# Neuro.net
KiCad netlist of a schematic drawn in EAGLE
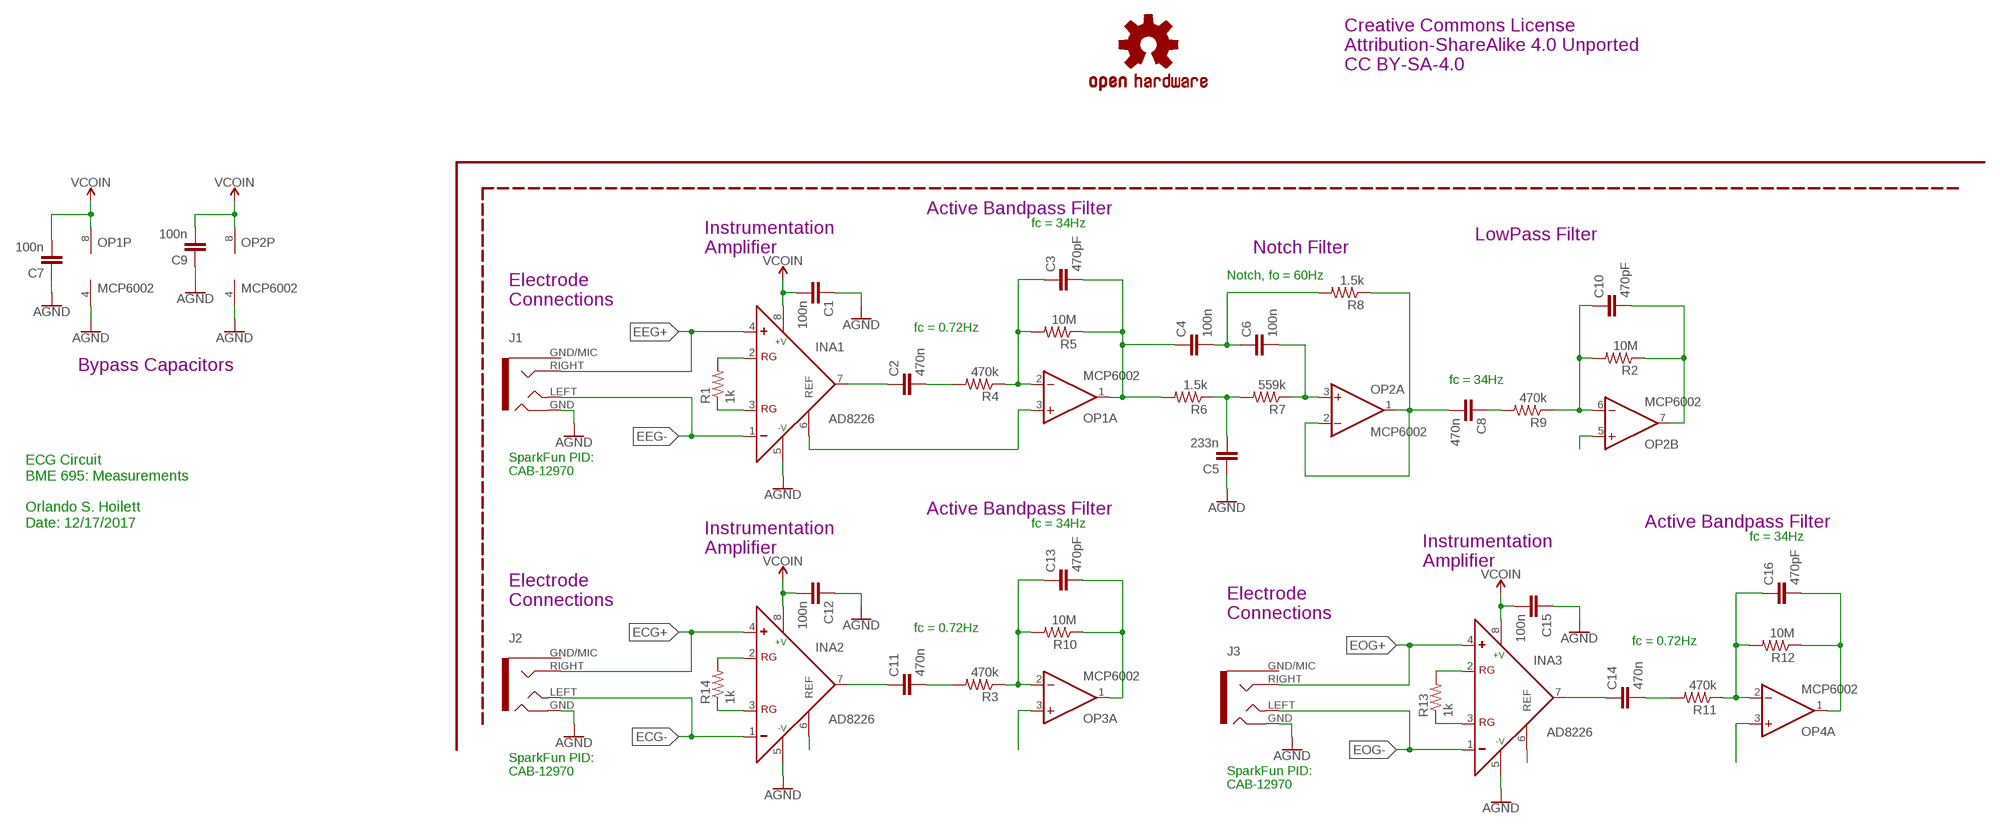
[diagram p0: schematic, sheet 1]

(export (version "E")
  (design (tool "Eeschema 10.0.6"))
  (components
    (comp (ref "C1")
      (value "100n")
      (footprint "eagle-import:C0402")
      (libsource (lib "eagle-import") (part "CAPACITOR0402"))
    )
    (comp (ref "C2")
      (value "470n")
      (footprint "eagle-import:C0402")
      (libsource (lib "eagle-import") (part "CAPACITOR0402"))
    )
    (comp (ref "C3")
      (value "470pF")
      (footprint "eagle-import:C0402")
      (libsource (lib "eagle-import") (part "CAPACITOR0402"))
    )
    (comp (ref "C4")
      (value "100n")
      (footprint "eagle-import:C0402")
      (libsource (lib "eagle-import") (part "CAPACITOR0402"))
    )
    (comp (ref "C5")
      (value "233n")
      (footprint "eagle-import:C0402")
      (libsource (lib "eagle-import") (part "CAPACITOR0402"))
    )
    (comp (ref "C6")
      (value "100n")
      (footprint "eagle-import:C0402")
      (libsource (lib "eagle-import") (part "CAPACITOR0402"))
    )
    (comp (ref "C7")
      (value "100n")
      (footprint "eagle-import:C0402")
      (libsource (lib "eagle-import") (part "CAPACITOR0402"))
    )
    (comp (ref "C8")
      (value "470n")
      (footprint "eagle-import:C0402")
      (libsource (lib "eagle-import") (part "CAPACITOR0402"))
    )
    (comp (ref "C9")
      (value "100n")
      (footprint "eagle-import:C0402")
      (libsource (lib "eagle-import") (part "CAPACITOR0402"))
    )
    (comp (ref "C10")
      (value "470pF")
      (footprint "eagle-import:C0402")
      (libsource (lib "eagle-import") (part "CAPACITOR0402"))
    )
    (comp (ref "C11")
      (value "470n")
      (footprint "eagle-import:C0402")
      (libsource (lib "eagle-import") (part "CAPACITOR0402"))
    )
    (comp (ref "C12")
      (value "100n")
      (footprint "eagle-import:C0402")
      (libsource (lib "eagle-import") (part "CAPACITOR0402"))
    )
    (comp (ref "C13")
      (value "470pF")
      (footprint "eagle-import:C0402")
      (libsource (lib "eagle-import") (part "CAPACITOR0402"))
    )
    (comp (ref "C14")
      (value "470n")
      (footprint "eagle-import:C0402")
      (libsource (lib "eagle-import") (part "CAPACITOR0402"))
    )
    (comp (ref "C15")
      (value "100n")
      (footprint "eagle-import:C0402")
      (libsource (lib "eagle-import") (part "CAPACITOR0402"))
    )
    (comp (ref "C16")
      (value "470pF")
      (footprint "eagle-import:C0402")
      (libsource (lib "eagle-import") (part "CAPACITOR0402"))
    )
    (comp (ref "INA1")
      (value "AD8226")
      (footprint "eagle-import:MSOP08")
      (libsource (lib "eagle-import") (part "INA-A"))
    )
    (comp (ref "INA2")
      (value "AD8226")
      (footprint "eagle-import:MSOP08")
      (libsource (lib "eagle-import") (part "INA-A"))
    )
    (comp (ref "INA3")
      (value "AD8226")
      (footprint "eagle-import:MSOP08")
      (libsource (lib "eagle-import") (part "INA-A"))
    )
    (comp (ref "J1")
      (value "AUDIO_JACK_TRRSSMD_RA")
      (footprint "eagle-import:AUDIO_JACK_3.5MM_TRRS_SMD_RA")
      (libsource (lib "eagle-import") (part "AUDIO_JACK_TRRSSMD_RA"))
    )
    (comp (ref "J2")
      (value "AUDIO_JACK_TRRSSMD_RA")
      (footprint "eagle-import:AUDIO_JACK_3.5MM_TRRS_SMD_RA")
      (libsource (lib "eagle-import") (part "AUDIO_JACK_TRRSSMD_RA"))
    )
    (comp (ref "J3")
      (value "AUDIO_JACK_TRRSSMD_RA")
      (footprint "eagle-import:AUDIO_JACK_3.5MM_TRRS_SMD_RA")
      (libsource (lib "eagle-import") (part "AUDIO_JACK_TRRSSMD_RA"))
    )
    (comp (ref "LOGO1")
      (value "OSHW-LOGOS")
      (footprint "eagle-import:OSHW-LOGO-S")
      (libsource (lib "eagle-import") (part "OSHW-LOGOS"))
    )
    (comp (ref "OP1")
      (value "MCP6002")
      (footprint "eagle-import:MSOP08")
      (fields (field (name "MF") "ALTERA CORPORATION") (field (name "MPN") "AD8607ARMZ-REEL"))
      (libsource (lib "eagle-import") (part "OP-DUALRM"))
    )
    (comp (ref "OP2")
      (value "MCP6002")
      (footprint "eagle-import:MSOP08")
      (fields (field (name "MF") "ALTERA CORPORATION") (field (name "MPN") "AD8607ARMZ-REEL"))
      (libsource (lib "eagle-import") (part "OP-DUALRM"))
    )
    (comp (ref "OP3")
      (value "MCP6002")
      (footprint "eagle-import:MSOP08")
      (fields (field (name "MF") "ALTERA CORPORATION") (field (name "MPN") "AD8607ARMZ-REEL"))
      (libsource (lib "eagle-import") (part "OP-DUALRM"))
    )
    (comp (ref "OP4")
      (value "MCP6002")
      (footprint "eagle-import:MSOP08")
      (fields (field (name "MF") "ALTERA CORPORATION") (field (name "MPN") "AD8607ARMZ-REEL"))
      (libsource (lib "eagle-import") (part "OP-DUALRM"))
    )
    (comp (ref "R1")
      (value "1k")
      (footprint "eagle-import:R0402")
      (libsource (lib "eagle-import") (part "RESISTOR0402"))
    )
    (comp (ref "R2")
      (value "10M")
      (footprint "eagle-import:R0402")
      (libsource (lib "eagle-import") (part "RESISTOR0402"))
    )
    (comp (ref "R3")
      (value "470k")
      (footprint "eagle-import:R0402")
      (libsource (lib "eagle-import") (part "RESISTOR0402"))
    )
    (comp (ref "R4")
      (value "470k")
      (footprint "eagle-import:R0402")
      (libsource (lib "eagle-import") (part "RESISTOR0402"))
    )
    (comp (ref "R5")
      (value "10M")
      (footprint "eagle-import:R0402")
      (libsource (lib "eagle-import") (part "RESISTOR0402"))
    )
    (comp (ref "R6")
      (value "1.5k")
      (footprint "eagle-import:R0402")
      (libsource (lib "eagle-import") (part "RESISTOR0402"))
    )
    (comp (ref "R7")
      (value "559k")
      (footprint "eagle-import:R0402")
      (libsource (lib "eagle-import") (part "RESISTOR0402"))
    )
    (comp (ref "R8")
      (value "1.5k")
      (footprint "eagle-import:R0402")
      (libsource (lib "eagle-import") (part "RESISTOR0402"))
    )
    (comp (ref "R9")
      (value "470k")
      (footprint "eagle-import:R0402")
      (libsource (lib "eagle-import") (part "RESISTOR0402"))
    )
    (comp (ref "R10")
      (value "10M")
      (footprint "eagle-import:R0402")
      (libsource (lib "eagle-import") (part "RESISTOR0402"))
    )
    (comp (ref "R11")
      (value "470k")
      (footprint "eagle-import:R0402")
      (libsource (lib "eagle-import") (part "RESISTOR0402"))
    )
    (comp (ref "R12")
      (value "10M")
      (footprint "eagle-import:R0402")
      (libsource (lib "eagle-import") (part "RESISTOR0402"))
    )
    (comp (ref "R13")
      (value "1k")
      (footprint "eagle-import:R0402")
      (libsource (lib "eagle-import") (part "RESISTOR0402"))
    )
    (comp (ref "R14")
      (value "1k")
      (footprint "eagle-import:R0402")
      (libsource (lib "eagle-import") (part "RESISTOR0402"))
    )
  )
  (nets
    (net (code "1") (name "AGND") (class "Default")
      (node (ref "C1") (pin "1") (pinfunction "1_1") (pintype "passive"))
      (node (ref "C12") (pin "1") (pinfunction "1_1") (pintype "passive"))
      (node (ref "C15") (pin "1") (pinfunction "1_1") (pintype "passive"))
      (node (ref "C5") (pin "1") (pinfunction "1_1") (pintype "passive"))
      (node (ref "C7") (pin "1") (pinfunction "1_1") (pintype "passive"))
      (node (ref "C9") (pin "1") (pinfunction "1_1") (pintype "passive"))
      (node (ref "INA1") (pin "5") (pinfunction "-V_5") (pintype "power_in"))
      (node (ref "INA2") (pin "5") (pinfunction "-V_5") (pintype "power_in"))
      (node (ref "INA3") (pin "5") (pinfunction "-V_5") (pintype "power_in"))
      (node (ref "J1") (pin "GND") (pinfunction "RING2_GND") (pintype "bidirectional"))
      (node (ref "J2") (pin "GND") (pinfunction "RING2_GND") (pintype "bidirectional"))
      (node (ref "J3") (pin "GND") (pinfunction "RING2_GND") (pintype "bidirectional"))
      (node (ref "OP1") (pin "4") (pinfunction "V-_4") (pintype "power_in"))
      (node (ref "OP2") (pin "4") (pinfunction "V-_4") (pintype "power_in"))
    )
    (net (code "2") (name "ECG+") (class "Default")
      (node (ref "INA2") (pin "4") (pinfunction "IN+_4") (pintype "input"))
      (node (ref "J2") (pin "RIGHT") (pinfunction "RING1_RIGHT") (pintype "bidirectional"))
    )
    (net (code "3") (name "ECG-") (class "Default")
      (node (ref "INA2") (pin "1") (pinfunction "IN-_1") (pintype "input"))
      (node (ref "J2") (pin "LEFT") (pinfunction "TIP_LEFT") (pintype "bidirectional"))
    )
    (net (code "4") (name "EEG+") (class "Default")
      (node (ref "INA1") (pin "4") (pinfunction "IN+_4") (pintype "input"))
      (node (ref "J1") (pin "RIGHT") (pinfunction "RING1_RIGHT") (pintype "bidirectional"))
    )
    (net (code "5") (name "EEG-") (class "Default")
      (node (ref "INA1") (pin "1") (pinfunction "IN-_1") (pintype "input"))
      (node (ref "J1") (pin "LEFT") (pinfunction "TIP_LEFT") (pintype "bidirectional"))
    )
    (net (code "6") (name "EOG+") (class "Default")
      (node (ref "INA3") (pin "4") (pinfunction "IN+_4") (pintype "input"))
      (node (ref "J3") (pin "RIGHT") (pinfunction "RING1_RIGHT") (pintype "bidirectional"))
    )
    (net (code "7") (name "EOG-") (class "Default")
      (node (ref "INA3") (pin "1") (pinfunction "IN-_1") (pintype "input"))
      (node (ref "J3") (pin "LEFT") (pinfunction "TIP_LEFT") (pintype "bidirectional"))
    )
    (net (code "8") (name "Net-(C2-Pad2)") (class "Default")
      (node (ref "C2") (pin "2") (pinfunction "2_2") (pintype "passive"))
      (node (ref "R4") (pin "2") (pinfunction "2_2") (pintype "passive"))
    )
    (net (code "9") (name "Net-(C4-Pad2)") (class "Default")
      (node (ref "C4") (pin "2") (pinfunction "2_2") (pintype "passive"))
      (node (ref "C6") (pin "1") (pinfunction "1_1") (pintype "passive"))
      (node (ref "R8") (pin "2") (pinfunction "2_2") (pintype "passive"))
    )
    (net (code "10") (name "Net-(C5-Pad2)") (class "Default")
      (node (ref "C5") (pin "2") (pinfunction "2_2") (pintype "passive"))
      (node (ref "R6") (pin "1") (pinfunction "1_1") (pintype "passive"))
      (node (ref "R7") (pin "2") (pinfunction "2_2") (pintype "passive"))
    )
    (net (code "11") (name "Net-(C8-Pad1)") (class "Default")
      (node (ref "C8") (pin "1") (pinfunction "1_1") (pintype "passive"))
      (node (ref "R9") (pin "2") (pinfunction "2_2") (pintype "passive"))
    )
    (net (code "12") (name "Net-(C11-Pad2)") (class "Default")
      (node (ref "C11") (pin "2") (pinfunction "2_2") (pintype "passive"))
      (node (ref "R3") (pin "2") (pinfunction "2_2") (pintype "passive"))
    )
    (net (code "13") (name "Net-(C14-Pad2)") (class "Default")
      (node (ref "C14") (pin "2") (pinfunction "2_2") (pintype "passive"))
      (node (ref "R11") (pin "2") (pinfunction "2_2") (pintype "passive"))
    )
    (net (code "14") (name "Net-(INA1-OUT)") (class "Default")
      (node (ref "C2") (pin "1") (pinfunction "1_1") (pintype "passive"))
      (node (ref "INA1") (pin "7") (pinfunction "OUT_7") (pintype "output"))
    )
    (net (code "15") (name "Net-(INA1-REF)") (class "Default")
      (node (ref "INA1") (pin "6") (pinfunction "REF_6") (pintype "passive"))
      (node (ref "OP1") (pin "3") (pinfunction "+IN_3") (pintype "input"))
    )
    (net (code "16") (name "Net-(INA1-RG-Pad2)") (class "Default")
      (node (ref "INA1") (pin "2") (pinfunction "RG_2") (pintype "passive"))
      (node (ref "R1") (pin "2") (pinfunction "2_2") (pintype "passive"))
    )
    (net (code "17") (name "Net-(INA1-RG-Pad3)") (class "Default")
      (node (ref "INA1") (pin "3") (pinfunction "RG_3") (pintype "passive"))
      (node (ref "R1") (pin "1") (pinfunction "1_1") (pintype "passive"))
    )
    (net (code "18") (name "Net-(INA2-OUT)") (class "Default")
      (node (ref "C11") (pin "1") (pinfunction "1_1") (pintype "passive"))
      (node (ref "INA2") (pin "7") (pinfunction "OUT_7") (pintype "output"))
    )
    (net (code "19") (name "Net-(INA2-RG-Pad2)") (class "Default")
      (node (ref "INA2") (pin "2") (pinfunction "RG_2") (pintype "passive"))
      (node (ref "R14") (pin "2") (pinfunction "2_2") (pintype "passive"))
    )
    (net (code "20") (name "Net-(INA2-RG-Pad3)") (class "Default")
      (node (ref "INA2") (pin "3") (pinfunction "RG_3") (pintype "passive"))
      (node (ref "R14") (pin "1") (pinfunction "1_1") (pintype "passive"))
    )
    (net (code "21") (name "Net-(INA3-OUT)") (class "Default")
      (node (ref "C14") (pin "1") (pinfunction "1_1") (pintype "passive"))
      (node (ref "INA3") (pin "7") (pinfunction "OUT_7") (pintype "output"))
    )
    (net (code "22") (name "Net-(INA3-RG-Pad2)") (class "Default")
      (node (ref "INA3") (pin "2") (pinfunction "RG_2") (pintype "passive"))
      (node (ref "R13") (pin "2") (pinfunction "2_2") (pintype "passive"))
    )
    (net (code "23") (name "Net-(INA3-RG-Pad3)") (class "Default")
      (node (ref "INA3") (pin "3") (pinfunction "RG_3") (pintype "passive"))
      (node (ref "R13") (pin "1") (pinfunction "1_1") (pintype "passive"))
    )
    (net (code "24") (name "Net-(OP1A--IN)") (class "Default")
      (node (ref "C3") (pin "1") (pinfunction "1_1") (pintype "passive"))
      (node (ref "OP1") (pin "2") (pinfunction "-IN_2") (pintype "input"))
      (node (ref "R4") (pin "1") (pinfunction "1_1") (pintype "passive"))
      (node (ref "R5") (pin "2") (pinfunction "2_2") (pintype "passive"))
    )
    (net (code "25") (name "Net-(OP1A-OUT)") (class "Default")
      (node (ref "C3") (pin "2") (pinfunction "2_2") (pintype "passive"))
      (node (ref "C4") (pin "1") (pinfunction "1_1") (pintype "passive"))
      (node (ref "OP1") (pin "1") (pinfunction "OUT_1") (pintype "output"))
      (node (ref "R5") (pin "1") (pinfunction "1_1") (pintype "passive"))
      (node (ref "R6") (pin "2") (pinfunction "2_2") (pintype "passive"))
    )
    (net (code "26") (name "Net-(OP2A-+IN)") (class "Default")
      (node (ref "C6") (pin "2") (pinfunction "2_2") (pintype "passive"))
      (node (ref "OP2") (pin "3") (pinfunction "+IN_3") (pintype "input"))
      (node (ref "R7") (pin "1") (pinfunction "1_1") (pintype "passive"))
    )
    (net (code "27") (name "Net-(OP2A--IN)") (class "Default")
      (node (ref "C8") (pin "2") (pinfunction "2_2") (pintype "passive"))
      (node (ref "OP2") (pin "1") (pinfunction "OUT_1") (pintype "output"))
      (node (ref "OP2") (pin "2") (pinfunction "-IN_2") (pintype "input"))
      (node (ref "R8") (pin "1") (pinfunction "1_1") (pintype "passive"))
    )
    (net (code "28") (name "Net-(OP2B--IN)") (class "Default")
      (node (ref "C10") (pin "1") (pinfunction "1_1") (pintype "passive"))
      (node (ref "OP2") (pin "6") (pinfunction "-IN_6") (pintype "input"))
      (node (ref "R2") (pin "2") (pinfunction "2_2") (pintype "passive"))
      (node (ref "R9") (pin "1") (pinfunction "1_1") (pintype "passive"))
    )
    (net (code "29") (name "Net-(OP2B-OUT)") (class "Default")
      (node (ref "C10") (pin "2") (pinfunction "2_2") (pintype "passive"))
      (node (ref "OP2") (pin "7") (pinfunction "OUT_7") (pintype "output"))
      (node (ref "R2") (pin "1") (pinfunction "1_1") (pintype "passive"))
    )
    (net (code "30") (name "Net-(OP3A--IN)") (class "Default")
      (node (ref "C13") (pin "1") (pinfunction "1_1") (pintype "passive"))
      (node (ref "OP3") (pin "2") (pinfunction "-IN_2") (pintype "input"))
      (node (ref "R10") (pin "2") (pinfunction "2_2") (pintype "passive"))
      (node (ref "R3") (pin "1") (pinfunction "1_1") (pintype "passive"))
    )
    (net (code "31") (name "Net-(OP3A-OUT)") (class "Default")
      (node (ref "C13") (pin "2") (pinfunction "2_2") (pintype "passive"))
      (node (ref "OP3") (pin "1") (pinfunction "OUT_1") (pintype "output"))
      (node (ref "R10") (pin "1") (pinfunction "1_1") (pintype "passive"))
    )
    (net (code "32") (name "Net-(OP4A--IN)") (class "Default")
      (node (ref "C16") (pin "1") (pinfunction "1_1") (pintype "passive"))
      (node (ref "OP4") (pin "2") (pinfunction "-IN_2") (pintype "input"))
      (node (ref "R11") (pin "1") (pinfunction "1_1") (pintype "passive"))
      (node (ref "R12") (pin "2") (pinfunction "2_2") (pintype "passive"))
    )
    (net (code "33") (name "Net-(OP4A-OUT)") (class "Default")
      (node (ref "C16") (pin "2") (pinfunction "2_2") (pintype "passive"))
      (node (ref "OP4") (pin "1") (pinfunction "OUT_1") (pintype "output"))
      (node (ref "R12") (pin "1") (pinfunction "1_1") (pintype "passive"))
    )
    (net (code "34") (name "VCOIN") (class "Default")
      (node (ref "C1") (pin "2") (pinfunction "2_2") (pintype "passive"))
      (node (ref "C12") (pin "2") (pinfunction "2_2") (pintype "passive"))
      (node (ref "C15") (pin "2") (pinfunction "2_2") (pintype "passive"))
      (node (ref "C7") (pin "2") (pinfunction "2_2") (pintype "passive"))
      (node (ref "C9") (pin "2") (pinfunction "2_2") (pintype "passive"))
      (node (ref "INA1") (pin "8") (pinfunction "+V_8") (pintype "power_in"))
      (node (ref "INA2") (pin "8") (pinfunction "+V_8") (pintype "power_in"))
      (node (ref "INA3") (pin "8") (pinfunction "+V_8") (pintype "power_in"))
      (node (ref "OP1") (pin "8") (pinfunction "V+_8") (pintype "power_in"))
      (node (ref "OP2") (pin "8") (pinfunction "V+_8") (pintype "power_in"))
    )
    (net (code "35") (name "unconnected-(INA2-REF-Pad6)") (class "Default")
      (node (ref "INA2") (pin "6") (pinfunction "REF_6") (pintype "passive"))
    )
    (net (code "36") (name "unconnected-(INA3-REF-Pad6)") (class "Default")
      (node (ref "INA3") (pin "6") (pinfunction "REF_6") (pintype "passive"))
    )
    (net (code "37") (name "unconnected-(J1-SLEEVE-PadGND{slash}MIC)") (class "Default")
      (node (ref "J1") (pin "GND/MIC") (pinfunction "SLEEVE_GND/MIC") (pintype "bidirectional"))
    )
    (net (code "38") (name "unconnected-(J2-SLEEVE-PadGND{slash}MIC)") (class "Default")
      (node (ref "J2") (pin "GND/MIC") (pinfunction "SLEEVE_GND/MIC") (pintype "bidirectional"))
    )
    (net (code "39") (name "unconnected-(J3-SLEEVE-PadGND{slash}MIC)") (class "Default")
      (node (ref "J3") (pin "GND/MIC") (pinfunction "SLEEVE_GND/MIC") (pintype "bidirectional"))
    )
    (net (code "40") (name "unconnected-(OP2B-+IN-Pad5)") (class "Default")
      (node (ref "OP2") (pin "5") (pinfunction "+IN_5") (pintype "input"))
    )
    (net (code "41") (name "unconnected-(OP3A-+IN-Pad3)") (class "Default")
      (node (ref "OP3") (pin "3") (pinfunction "+IN_3") (pintype "input"))
    )
    (net (code "42") (name "unconnected-(OP4A-+IN-Pad3)") (class "Default")
      (node (ref "OP4") (pin "3") (pinfunction "+IN_3") (pintype "input"))
    )
  )
)
